# Schematic.net
KiCad netlist of a schematic drawn in Altium Designer
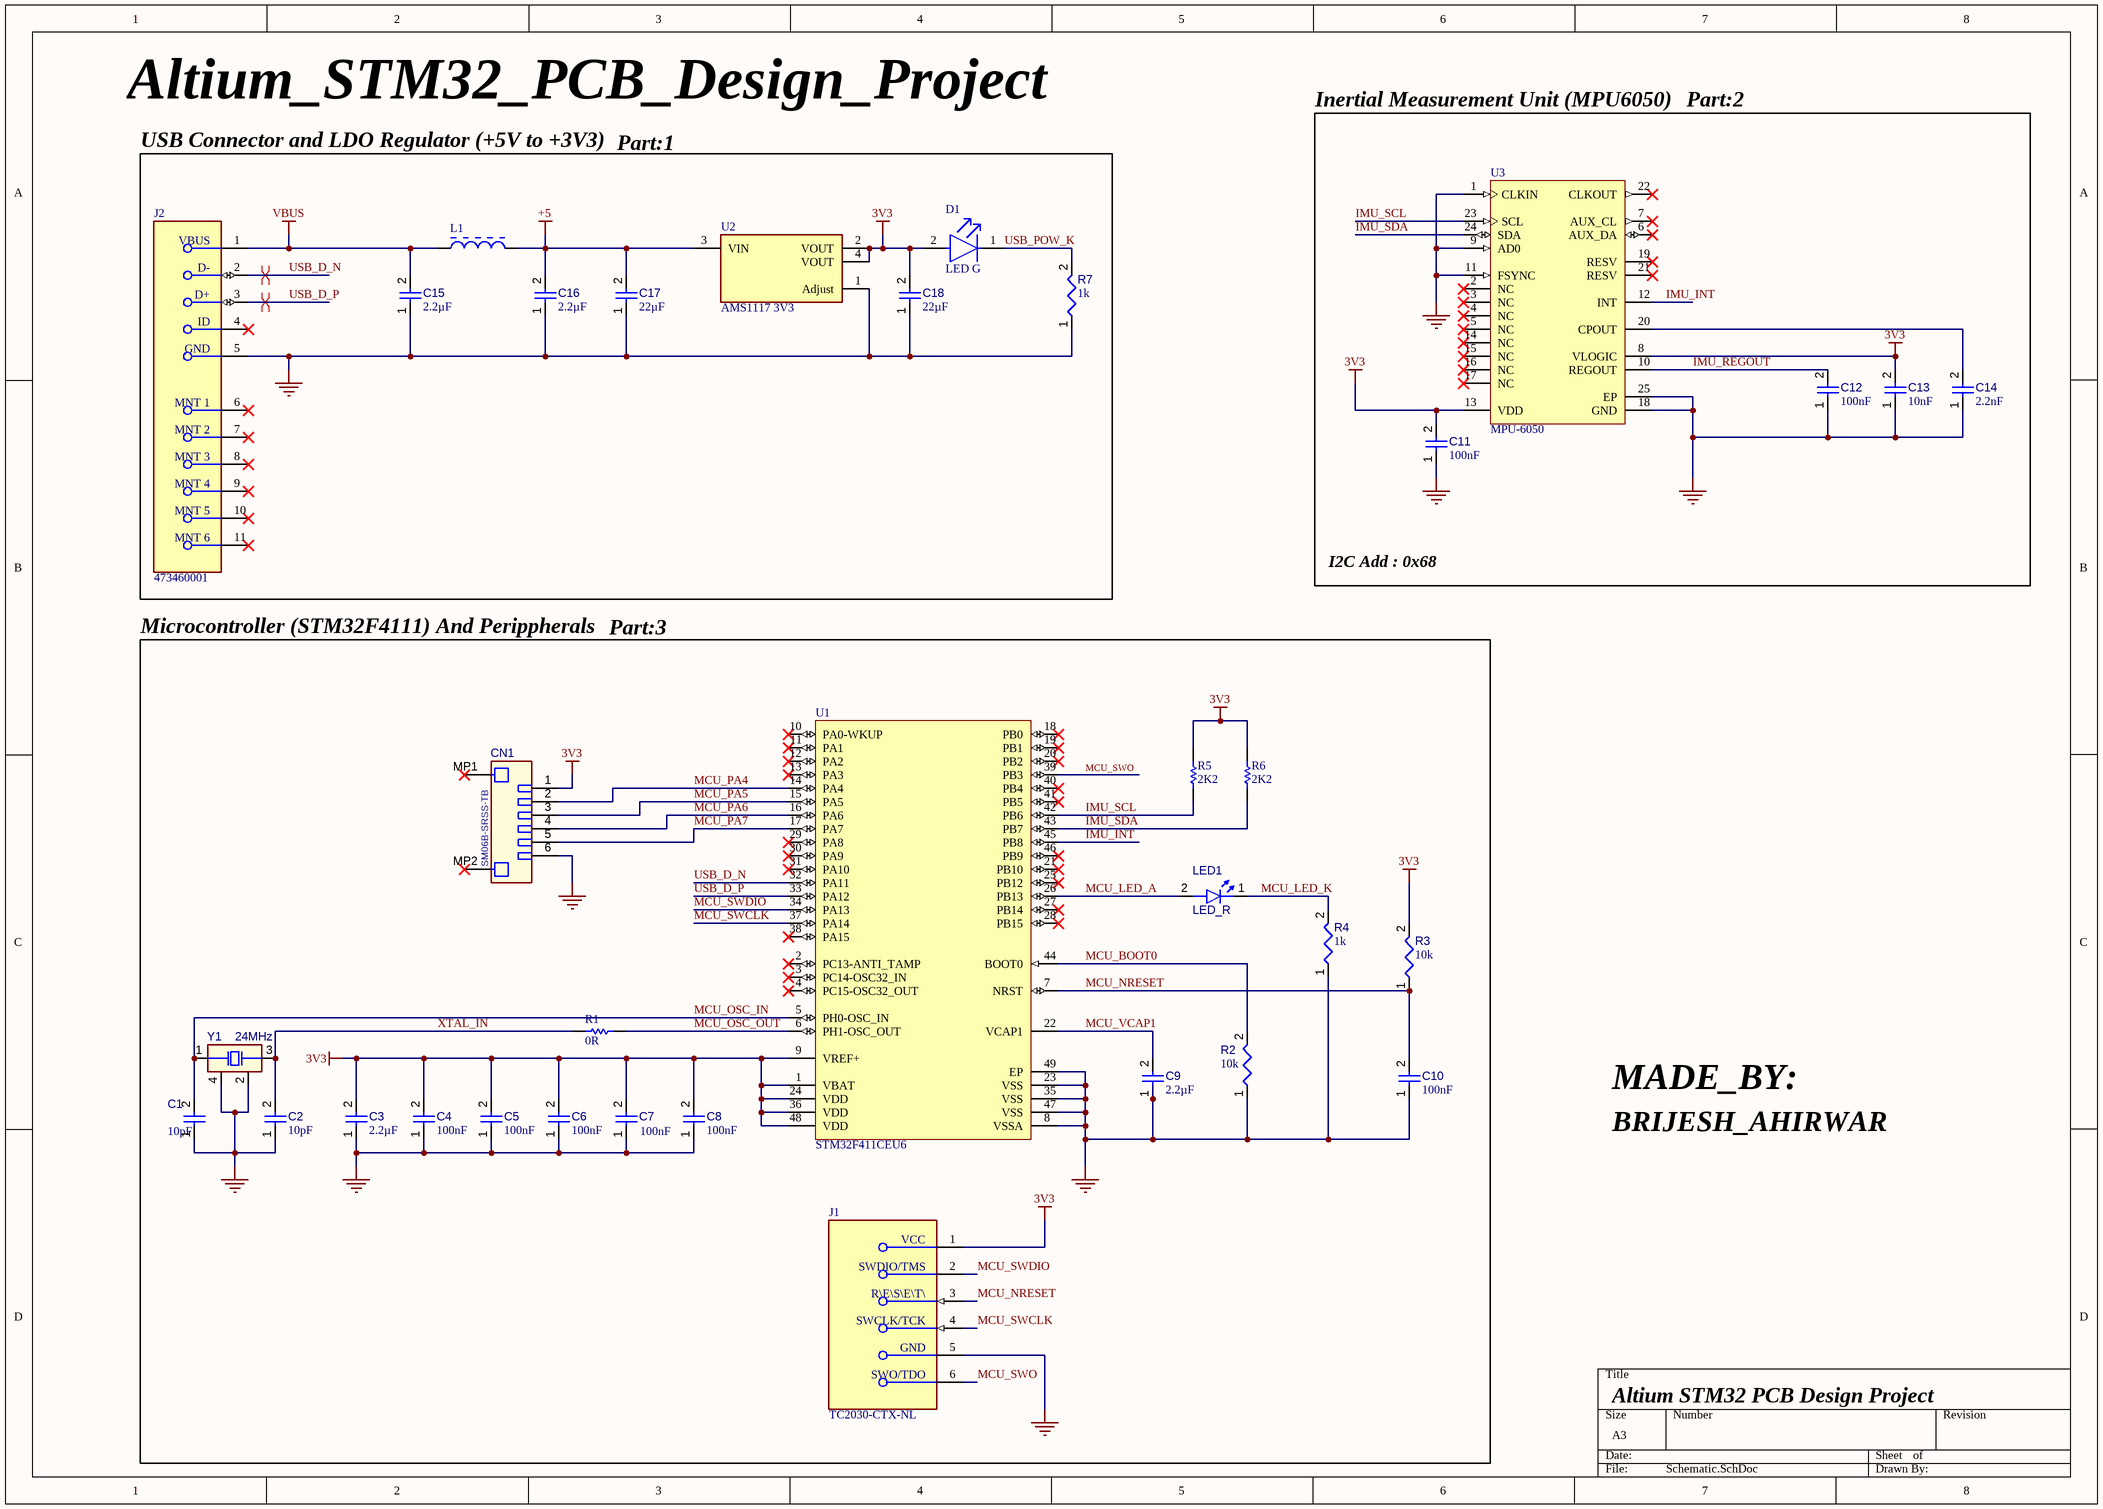
[diagram p0: Schematic.SchDoc]

(export (version "E")
  (design (tool "Eeschema 10.0.6"))
  (components
    (comp (ref "C1")
      (value "10pF")
      (footprint "CAPC1608X90X40ML10T20")
      (description "Chip Capacitor, 10 pF, +/- 5%, 50 V, 0603 (1608 Metric)")
      (fields (field (name "TOLERANCE") "5%") (field (name "Comment") "Capacitor 10 pF +/- 5% 50 V 0603"))
      (libsource (lib "IIT_BHU_Varanasi") (part "CAP-NP-2"))
    )
    (comp (ref "C2")
      (value "10pF")
      (footprint "CAPC1608X90X40ML10T20")
      (description "Chip Capacitor, 10 pF, +/- 5%, 50 V, 0603 (1608 Metric)")
      (fields (field (name "TOLERANCE") "5%") (field (name "Comment") "Capacitor 10 pF +/- 5% 50 V 0603"))
      (libsource (lib "IIT_BHU_Varanasi") (part "CAP-NP-2"))
    )
    (comp (ref "C3")
      (value "2.2µF")
      (footprint "CAPC0603(1608)100_L")
      (description "Chip Capacitor, 10µF +/-20%, 10V, 0603, Thickness 1 mm")
      (fields (field (name "TOLERANCE") "10%") (field (name "Comment") "Capacitor 10µF +/-20% 10V 0603"))
      (libsource (lib "IIT_BHU_Varanasi") (part "CAP-NP-2"))
    )
    (comp (ref "C4")
      (value "100nF")
      (footprint "CAPC1005X56X25LL10T15")
      (description "Chip Capacitor, 0.1 uF, +/- 5%, 16 V, 0402 (1005 Metric)")
      (fields (field (name "TOLERANCE") "5%") (field (name "Comment") "Capacitor 0.1 uF +/- 5% 16 V 0402"))
      (libsource (lib "IIT_BHU_Varanasi") (part "CAP-NP-2"))
    )
    (comp (ref "C5")
      (value "100nF")
      (footprint "CAPC1005X56X25LL10T15")
      (description "Chip Capacitor, 0.1 uF, +/- 5%, 16 V, 0402 (1005 Metric)")
      (fields (field (name "TOLERANCE") "5%") (field (name "Comment") "Capacitor 0.1 uF +/- 5% 16 V 0402"))
      (libsource (lib "IIT_BHU_Varanasi") (part "CAP-NP-2"))
    )
    (comp (ref "C6")
      (value "100nF")
      (footprint "CAPC1005X56X25LL10T15")
      (description "Chip Capacitor, 0.1 uF, +/- 5%, 16 V, 0402 (1005 Metric)")
      (fields (field (name "TOLERANCE") "5%") (field (name "Comment") "Capacitor 0.1 uF +/- 5% 16 V 0402"))
      (libsource (lib "IIT_BHU_Varanasi") (part "CAP-NP-2"))
    )
    (comp (ref "C7")
      (value "100nF")
      (footprint "CAPC1005X56X25LL10T15")
      (description "Chip Capacitor, 0.1 uF, +/- 5%, 16 V, 0402 (1005 Metric)")
      (fields (field (name "TOLERANCE") "5%") (field (name "Comment") "Capacitor 0.1 uF +/- 5% 16 V 0402"))
      (libsource (lib "IIT_BHU_Varanasi") (part "CAP-NP-2"))
    )
    (comp (ref "C8")
      (value "100nF")
      (footprint "CAPC1005X56X25LL10T15")
      (description "Chip Capacitor, 0.1 uF, +/- 5%, 16 V, 0402 (1005 Metric)")
      (fields (field (name "TOLERANCE") "5%") (field (name "Comment") "Capacitor 0.1 uF +/- 5% 16 V 0402"))
      (libsource (lib "IIT_BHU_Varanasi") (part "CAP-NP-2"))
    )
    (comp (ref "C9")
      (value "2.2µF")
      (footprint "CAPC0603(1608)100_L")
      (description "Chip Capacitor, 10µF +/-20%, 10V, 0603, Thickness 1 mm")
      (fields (field (name "TOLERANCE") "10%") (field (name "Comment") "Capacitor 10µF +/-20% 10V 0603"))
      (libsource (lib "IIT_BHU_Varanasi") (part "CAP-NP-2"))
    )
    (comp (ref "C10")
      (value "100nF")
      (footprint "CAPC1005X56X25LL10T15")
      (description "Chip Capacitor, 0.1 uF, +/- 5%, 16 V, 0402 (1005 Metric)")
      (fields (field (name "TOLERANCE") "5%") (field (name "Comment") "Capacitor 0.1 uF +/- 5% 16 V 0402"))
      (libsource (lib "IIT_BHU_Varanasi") (part "CAP-NP-2"))
    )
    (comp (ref "C11")
      (value "100nF")
      (footprint "CAPC1005X56X25LL10T15")
      (description "Chip Capacitor, 0.1 uF, +/- 5%, 16 V, 0402 (1005 Metric)")
      (fields (field (name "TOLERANCE") "5%") (field (name "Comment") "Capacitor 0.1 uF +/- 5% 16 V 0402"))
      (libsource (lib "IIT_BHU_Varanasi") (part "CAP-NP-2"))
    )
    (comp (ref "C12")
      (value "100nF")
      (footprint "CAPC1005X56X25LL10T15")
      (description "Chip Capacitor, 0.1 uF, +/- 5%, 16 V, 0402 (1005 Metric)")
      (fields (field (name "TOLERANCE") "5%") (field (name "Comment") "Capacitor 0.1 uF +/- 5% 16 V 0402"))
      (libsource (lib "IIT_BHU_Varanasi") (part "CAP-NP-2"))
    )
    (comp (ref "C13")
      (value "10nF")
      (footprint "CAPC1005X56X25LL10T15")
      (description "Chip Capacitor, 0.1 uF, +/- 5%, 16 V, 0402 (1005 Metric)")
      (fields (field (name "TOLERANCE") "5%") (field (name "Comment") "Capacitor 0.1 uF +/- 5% 16 V 0402"))
      (libsource (lib "IIT_BHU_Varanasi") (part "CAP-NP-2"))
    )
    (comp (ref "C14")
      (value "2.2nF")
      (footprint "CAPC1005X56X25LL10T15")
      (description "Chip Capacitor, 0.1 uF, +/- 5%, 16 V, 0402 (1005 Metric)")
      (fields (field (name "TOLERANCE") "5%") (field (name "Comment") "Capacitor 0.1 uF +/- 5% 16 V 0402"))
      (libsource (lib "IIT_BHU_Varanasi") (part "CAP-NP-2"))
    )
    (comp (ref "C15")
      (value "2.2µF")
      (footprint "CAPC0603(1608)100_L")
      (description "Chip Capacitor, 10µF +/-20%, 10V, 0603, Thickness 1 mm")
      (fields (field (name "TOLERANCE") "10%") (field (name "Comment") "Capacitor 10µF +/-20% 10V 0603"))
      (libsource (lib "IIT_BHU_Varanasi") (part "CAP-NP-2"))
    )
    (comp (ref "C16")
      (value "2.2µF")
      (footprint "CAPC0603(1608)100_L")
      (description "Chip Capacitor, 10µF +/-20%, 10V, 0603, Thickness 1 mm")
      (fields (field (name "TOLERANCE") "10%") (field (name "Comment") "Capacitor 10µF +/-20% 10V 0603"))
      (libsource (lib "IIT_BHU_Varanasi") (part "CAP-NP-2"))
    )
    (comp (ref "C17")
      (value "22µF")
      (footprint "CAPC0603(1608)100_L")
      (description "Chip Capacitor, 10µF +/-20%, 10V, 0603, Thickness 1 mm")
      (fields (field (name "TOLERANCE") "10%") (field (name "Comment") "Capacitor 10µF +/-20% 10V 0603"))
      (libsource (lib "IIT_BHU_Varanasi") (part "CAP-NP-2"))
    )
    (comp (ref "C18")
      (value "22µF")
      (footprint "CAPC0603(1608)100_L")
      (description "Chip Capacitor, 10µF +/-20%, 10V, 0603, Thickness 1 mm")
      (fields (field (name "TOLERANCE") "10%") (field (name "Comment") "Capacitor 10µF +/-20% 10V 0603"))
      (libsource (lib "IIT_BHU_Varanasi") (part "CAP-NP-2"))
    )
    (comp (ref "CN1")
      (value "SM06B-SRSS-TB")
      (footprint "JST-SM06B-SRSS-TB_V")
      (description "Male Header, Pitch 1 mm, 1 x 6 Position, Height 2.95 mm, -25 to 85 degC, RoHS, Tape and Reel")
      (libsource (lib "IIT_BHU_Varanasi") (part "CMP-00143-5"))
    )
    (comp (ref "D1")
      (value "LED G")
      (footprint "FP-LG_Q396-MFG")
      (description "LED GREEN DIFFUSED 0603 SMD")
      (libsource (lib "Altium Content Vault") (part "8706943c75ba83719d021d2fdc84c58"))
    )
    (comp (ref "J1")
      (value "TC2030-CTX-NL")
      (footprint "FP-TC2030-CTX-NL-MFG")
      (description "6-Pin “No legs” TC2030 Plug-of-Nails™ Cable for use with ARM Cortex processors")
      (libsource (lib "Altium Content Vault") (part "e3fe093a55dc37473f431e03719485e"))
    )
    (comp (ref "J2")
      (value "473460001")
      (footprint "FP-473460001-MFG")
      (description "CONN RCPT USB2.0 MICRO B SMD R/A")
      (fields
        (field (name "OCTOPART") "https://octopart.com/47346-0001-molex-7164928")
        (field (name "MANUFACTURER") "Molex")
      )
      (libsource (lib "Altium Content Vault") (part "53ae1f1d9b557310b43ca686e5bb76a"))
    )
    (comp (ref "L1")
      (value "BLM18AG121SN1D")
      (footprint "MURA-BLM18-F-H1-CHIP-2_V")
      (fields (field (name "TOLERANCE") "25%") (field (name "MANUFACTURER") "Murata"))
      (libsource (lib "IIT_BHU_Varanasi") (part "IND-FB-2"))
    )
    (comp (ref "LED1")
      (value "LED_R")
      (footprint "QTB-QBLP595_V")
      (description "Chip LED 0402, Red, 0.02 A, 2.0 to 2.5 V, -40 to 80 degC, 2-Pin SMD, RoHS, Tape and Reel")
      (libsource (lib "IIT_BHU_Varanasi") (part "LED-KA-2"))
    )
    (comp (ref "R1")
      (value "0R")
      (footprint "RESC1005X40X25ML05T10")
      (description "Chip Resistor, 0 Ohm, 0.063 W, -55 to 155 degC, 0402 (1005 Metric)")
      (fields (field (name "POWER") "63mW") (field (name "Comment") "Resistor 0R 0402 63 mW"))
      (libsource (lib "") (part "RES-2_1"))
    )
    (comp (ref "R2")
      (value "10k")
      (footprint "RESC0402(1005)_L")
      (description "Chip Resistor, 10 kOhms, +/-1 %, 63 mW, -55 to 125 degC, 0402")
      (fields (field (name "POWER") "63mW") (field (name "TOLERANCE") "1%"))
      (libsource (lib "IIT_BHU_Varanasi") (part "RES-2"))
    )
    (comp (ref "R3")
      (value "10k")
      (footprint "RESC0402(1005)_L")
      (description "Chip Resistor, 10 kOhms, +/-1 %, 63 mW, -55 to 125 degC, 0402")
      (fields (field (name "POWER") "63mW") (field (name "TOLERANCE") "1%"))
      (libsource (lib "IIT_BHU_Varanasi") (part "RES-2"))
    )
    (comp (ref "R4")
      (value "1k")
      (footprint "RESC0402(1005)_L")
      (description "Chip Resistor, 1 kOhms, +/-5 %, 63 mW, -55 to 155 degC, 0402")
      (fields (field (name "TOLERANCE") "5%") (field (name "POWER") "63mW"))
      (libsource (lib "IIT_BHU_Varanasi") (part "RES-2"))
    )
    (comp (ref "R5")
      (value "2K2")
      (footprint "RESC0402(1005)_N")
      (description "2K2 0.063W 5% 0402 (1005 Metric)  SMD")
      (fields (field (name "TOLERANCE") "5 %") (field (name "POWER") "0.063 W"))
      (libsource (lib "Altium Content Vault") (part "RES"))
    )
    (comp (ref "R6")
      (value "2K2")
      (footprint "RESC0402(1005)_N")
      (description "2K2 0.063W 5% 0402 (1005 Metric)  SMD")
      (fields (field (name "TOLERANCE") "5 %") (field (name "POWER") "0.063 W"))
      (libsource (lib "Altium Content Vault") (part "RES"))
    )
    (comp (ref "R7")
      (value "1k")
      (footprint "RESC0402(1005)_L")
      (description "Chip Resistor, 1 kOhms, +/-5 %, 63 mW, -55 to 155 degC, 0402")
      (fields (field (name "TOLERANCE") "5%") (field (name "POWER") "63mW"))
      (libsource (lib "IIT_BHU_Varanasi") (part "RES-2"))
    )
    (comp (ref "U1")
      (value "STM32F411CEU6")
      (footprint "STM-UFQFPN48_L")
      (libsource (lib "Altium Content Vault") (part "MC-ARM-STM32F411-UFQFPN48"))
    )
    (comp (ref "U2")
      (value "AMS1117 3V3")
      (footprint "FP-ams1117-IPC_C")
      (description "1A LOW DROPOUT VOLTAGE REGULATOR")
      (libsource (lib "Altium Content Vault") (part "59ad430b93a2c51b3e6ee7c3b069677"))
    )
    (comp (ref "U3")
      (value "MPU-6050")
      (footprint "IS-QFN-24_V")
      (fields (field (name "MANUFACTURER") "InvenSense"))
      (libsource (lib "Altium Content Vault") (part "IS-MPU-6050-QFN-24"))
    )
    (comp (ref "Y1")
      (value "24MHz")
      (footprint "EPSON-FA-128_V")
      (description "Crystal, 24 MHz, +/- 10 ppm, -20 to 75 degC, 4-Pin SMD, RoHS, Tape and Reel")
      (libsource (lib "IIT_BHU_Varanasi") (part "CMP-00014-7"))
    )
  )
  (nets
    (net (code "1") (name "+5") (class "Default")
      (node (ref "C16") (pin "2") (pinfunction "2_2") (pintype "passive"))
      (node (ref "C17") (pin "2") (pinfunction "2_2") (pintype "passive"))
      (node (ref "L1") (pin "2") (pinfunction "2_2") (pintype "passive"))
      (node (ref "U2") (pin "3") (pinfunction "VIN_3") (pintype "power_in"))
    )
    (net (code "2") (name "/IMU_INT") (class "Default")
      (node (ref "U1") (pin "45") (pinfunction "PB8_45") (pintype "bidirectional"))
      (node (ref "U3") (pin "12") (pinfunction "INT_12") (pintype "open_collector"))
    )
    (net (code "3") (name "/IMU_REGOUT") (class "Default")
      (node (ref "C12") (pin "2") (pinfunction "2_2") (pintype "passive"))
      (node (ref "U3") (pin "10") (pinfunction "REGOUT_10") (pintype "passive"))
    )
    (net (code "4") (name "/IMU_SCL") (class "Default")
      (node (ref "R5") (pin "1") (pinfunction "1_1") (pintype "passive"))
      (node (ref "U1") (pin "42") (pinfunction "PB6_42") (pintype "bidirectional"))
      (node (ref "U3") (pin "23") (pinfunction "SCL_23") (pintype "input"))
    )
    (net (code "5") (name "/IMU_SDA") (class "Default")
      (node (ref "R6") (pin "1") (pinfunction "1_1") (pintype "passive"))
      (node (ref "U1") (pin "43") (pinfunction "PB7_43") (pintype "bidirectional"))
      (node (ref "U3") (pin "24") (pinfunction "SDA_24") (pintype "bidirectional"))
    )
    (net (code "6") (name "/MCU_BOOT0") (class "Default")
      (node (ref "R2") (pin "2") (pinfunction "2_2") (pintype "passive"))
      (node (ref "U1") (pin "44") (pinfunction "BOOT0_44") (pintype "input"))
    )
    (net (code "7") (name "/MCU_LED_A") (class "Default")
      (node (ref "LED1") (pin "2") (pinfunction "A_2") (pintype "passive"))
      (node (ref "U1") (pin "26") (pinfunction "PB13_26") (pintype "bidirectional"))
    )
    (net (code "8") (name "/MCU_LED_K") (class "Default")
      (node (ref "LED1") (pin "1") (pinfunction "K_1") (pintype "passive"))
      (node (ref "R4") (pin "2") (pinfunction "2_2") (pintype "passive"))
    )
    (net (code "9") (name "/MCU_NRESET") (class "Default")
      (node (ref "C10") (pin "2") (pinfunction "2_2") (pintype "passive"))
      (node (ref "J1") (pin "3") (pinfunction "~{RESET}_3") (pintype "input"))
      (node (ref "R3") (pin "1") (pinfunction "1_1") (pintype "passive"))
      (node (ref "U1") (pin "7") (pinfunction "NRST_7") (pintype "bidirectional"))
    )
    (net (code "10") (name "/MCU_OSC_IN") (class "Default")
      (node (ref "C1") (pin "2") (pinfunction "2_2") (pintype "passive"))
      (node (ref "U1") (pin "5") (pinfunction "PH0-OSC_IN_5") (pintype "bidirectional"))
      (node (ref "Y1") (pin "1") (pinfunction "X1_1") (pintype "passive"))
    )
    (net (code "11") (name "/MCU_OSC_OUT") (class "Default")
      (node (ref "R1") (pin "2") (pinfunction "2_2") (pintype "passive"))
      (node (ref "U1") (pin "6") (pinfunction "PH1-OSC_OUT_6") (pintype "bidirectional"))
    )
    (net (code "12") (name "/MCU_PA4") (class "Default")
      (node (ref "CN1") (pin "2") (pinfunction "2_2") (pintype "passive"))
      (node (ref "U1") (pin "14") (pinfunction "PA4_14") (pintype "bidirectional"))
    )
    (net (code "13") (name "/MCU_PA5") (class "Default")
      (node (ref "CN1") (pin "3") (pinfunction "3_3") (pintype "passive"))
      (node (ref "U1") (pin "15") (pinfunction "PA5_15") (pintype "bidirectional"))
    )
    (net (code "14") (name "/MCU_PA6") (class "Default")
      (node (ref "CN1") (pin "4") (pinfunction "4_4") (pintype "passive"))
      (node (ref "U1") (pin "16") (pinfunction "PA6_16") (pintype "bidirectional"))
    )
    (net (code "15") (name "/MCU_PA7") (class "Default")
      (node (ref "CN1") (pin "5") (pinfunction "5_5") (pintype "passive"))
      (node (ref "U1") (pin "17") (pinfunction "PA7_17") (pintype "bidirectional"))
    )
    (net (code "16") (name "/MCU_SWCLK") (class "Default")
      (node (ref "J1") (pin "4") (pinfunction "SWCLK/TCK_4") (pintype "input"))
      (node (ref "U1") (pin "37") (pinfunction "PA14_37") (pintype "bidirectional"))
    )
    (net (code "17") (name "/MCU_SWDIO") (class "Default")
      (node (ref "J1") (pin "2") (pinfunction "SWDIO/TMS_2") (pintype "passive"))
      (node (ref "U1") (pin "34") (pinfunction "PA13_34") (pintype "bidirectional"))
    )
    (net (code "18") (name "/MCU_SWO") (class "Default")
      (node (ref "J1") (pin "6") (pinfunction "SWO/TDO_6") (pintype "passive"))
      (node (ref "U1") (pin "39") (pinfunction "PB3_39") (pintype "bidirectional"))
    )
    (net (code "19") (name "/MCU_VCAP1") (class "Default")
      (node (ref "C9") (pin "2") (pinfunction "2_2") (pintype "passive"))
      (node (ref "U1") (pin "22") (pinfunction "VCAP1_22") (pintype "passive"))
    )
    (net (code "20") (name "/USB_D_N") (class "Default")
      (node (ref "J2") (pin "2") (pinfunction "D-_2") (pintype "bidirectional"))
      (node (ref "U1") (pin "32") (pinfunction "PA11_32") (pintype "bidirectional"))
    )
    (net (code "21") (name "/USB_D_P") (class "Default")
      (node (ref "J2") (pin "3") (pinfunction "D+_3") (pintype "bidirectional"))
      (node (ref "U1") (pin "33") (pinfunction "PA12_33") (pintype "bidirectional"))
    )
    (net (code "22") (name "/USB_POW_K") (class "Default")
      (node (ref "D1") (pin "1") (pinfunction "C_1") (pintype "passive"))
      (node (ref "R7") (pin "2") (pinfunction "2_2") (pintype "passive"))
    )
    (net (code "23") (name "/XTAL_IN") (class "Default")
      (node (ref "C2") (pin "2") (pinfunction "2_2") (pintype "passive"))
      (node (ref "R1") (pin "1") (pinfunction "1_1") (pintype "passive"))
      (node (ref "Y1") (pin "3") (pinfunction "X2_3") (pintype "passive"))
    )
    (net (code "24") (name "3V3") (class "Default")
      (node (ref "C11") (pin "2") (pinfunction "2_2") (pintype "passive"))
      (node (ref "C13") (pin "2") (pinfunction "2_2") (pintype "passive"))
      (node (ref "C18") (pin "2") (pinfunction "2_2") (pintype "passive"))
      (node (ref "C3") (pin "2") (pinfunction "2_2") (pintype "passive"))
      (node (ref "C4") (pin "2") (pinfunction "2_2") (pintype "passive"))
      (node (ref "C5") (pin "2") (pinfunction "2_2") (pintype "passive"))
      (node (ref "C6") (pin "2") (pinfunction "2_2") (pintype "passive"))
      (node (ref "C7") (pin "2") (pinfunction "2_2") (pintype "passive"))
      (node (ref "C8") (pin "2") (pinfunction "2_2") (pintype "passive"))
      (node (ref "CN1") (pin "1") (pinfunction "1_1") (pintype "passive"))
      (node (ref "D1") (pin "2") (pinfunction "A_2") (pintype "passive"))
      (node (ref "J1") (pin "1") (pinfunction "VCC_1") (pintype "power_in"))
      (node (ref "R3") (pin "2") (pinfunction "2_2") (pintype "passive"))
      (node (ref "R5") (pin "2") (pinfunction "2_2") (pintype "passive"))
      (node (ref "R6") (pin "2") (pinfunction "2_2") (pintype "passive"))
      (node (ref "U1") (pin "1") (pinfunction "VBAT_1") (pintype "power_in"))
      (node (ref "U1") (pin "24") (pinfunction "VDD_24") (pintype "power_in"))
      (node (ref "U1") (pin "36") (pinfunction "VDD_36") (pintype "power_in"))
      (node (ref "U1") (pin "48") (pinfunction "VDD_48") (pintype "power_in"))
      (node (ref "U1") (pin "9") (pinfunction "VREF+_9") (pintype "power_in"))
      (node (ref "U2") (pin "2") (pinfunction "VOUT_2") (pintype "passive"))
      (node (ref "U2") (pin "4") (pinfunction "VOUT_4") (pintype "passive"))
      (node (ref "U3") (pin "13") (pinfunction "VDD_13") (pintype "power_in"))
      (node (ref "U3") (pin "8") (pinfunction "VLOGIC_8") (pintype "power_in"))
    )
    (net (code "25") (name "GND") (class "Default")
      (node (ref "C1") (pin "1") (pinfunction "1_1") (pintype "passive"))
      (node (ref "C10") (pin "1") (pinfunction "1_1") (pintype "passive"))
      (node (ref "C11") (pin "1") (pinfunction "1_1") (pintype "passive"))
      (node (ref "C12") (pin "1") (pinfunction "1_1") (pintype "passive"))
      (node (ref "C13") (pin "1") (pinfunction "1_1") (pintype "passive"))
      (node (ref "C14") (pin "1") (pinfunction "1_1") (pintype "passive"))
      (node (ref "C15") (pin "1") (pinfunction "1_1") (pintype "passive"))
      (node (ref "C16") (pin "1") (pinfunction "1_1") (pintype "passive"))
      (node (ref "C17") (pin "1") (pinfunction "1_1") (pintype "passive"))
      (node (ref "C18") (pin "1") (pinfunction "1_1") (pintype "passive"))
      (node (ref "C2") (pin "1") (pinfunction "1_1") (pintype "passive"))
      (node (ref "C3") (pin "1") (pinfunction "1_1") (pintype "passive"))
      (node (ref "C4") (pin "1") (pinfunction "1_1") (pintype "passive"))
      (node (ref "C5") (pin "1") (pinfunction "1_1") (pintype "passive"))
      (node (ref "C6") (pin "1") (pinfunction "1_1") (pintype "passive"))
      (node (ref "C7") (pin "1") (pinfunction "1_1") (pintype "passive"))
      (node (ref "C8") (pin "1") (pinfunction "1_1") (pintype "passive"))
      (node (ref "C9") (pin "1") (pinfunction "1_1") (pintype "passive"))
      (node (ref "CN1") (pin "6") (pinfunction "6_6") (pintype "passive"))
      (node (ref "J1") (pin "5") (pinfunction "GND_5") (pintype "power_in"))
      (node (ref "J2") (pin "5") (pinfunction "GND_5") (pintype "power_in"))
      (node (ref "R2") (pin "1") (pinfunction "1_1") (pintype "passive"))
      (node (ref "R4") (pin "1") (pinfunction "1_1") (pintype "passive"))
      (node (ref "R7") (pin "1") (pinfunction "1_1") (pintype "passive"))
      (node (ref "U1") (pin "23") (pinfunction "VSS_23") (pintype "power_in"))
      (node (ref "U1") (pin "35") (pinfunction "VSS_35") (pintype "power_in"))
      (node (ref "U1") (pin "47") (pinfunction "VSS_47") (pintype "power_in"))
      (node (ref "U1") (pin "49") (pinfunction "EP_49") (pintype "power_in"))
      (node (ref "U1") (pin "8") (pinfunction "VSSA_8") (pintype "power_in"))
      (node (ref "U2") (pin "1") (pinfunction "Adjust_1") (pintype "passive"))
      (node (ref "U3") (pin "1") (pinfunction "CLKIN_1") (pintype "input"))
      (node (ref "U3") (pin "11") (pinfunction "FSYNC_11") (pintype "input"))
      (node (ref "U3") (pin "18") (pinfunction "GND_18") (pintype "power_in"))
      (node (ref "U3") (pin "25") (pinfunction "EP_25") (pintype "power_in"))
      (node (ref "U3") (pin "9") (pinfunction "AD0_9") (pintype "input"))
      (node (ref "Y1") (pin "2") (pinfunction "NC_2") (pintype "power_in"))
      (node (ref "Y1") (pin "4") (pinfunction "NC_4") (pintype "power_in"))
    )
    (net (code "26") (name "Net-(U3-CPOUT)") (class "Default")
      (node (ref "C14") (pin "2") (pinfunction "2_2") (pintype "passive"))
      (node (ref "U3") (pin "20") (pinfunction "CPOUT_20") (pintype "passive"))
    )
    (net (code "27") (name "VBUS") (class "Default")
      (node (ref "C15") (pin "2") (pinfunction "2_2") (pintype "passive"))
      (node (ref "J2") (pin "1") (pinfunction "VBUS_1") (pintype "power_in"))
      (node (ref "L1") (pin "1") (pinfunction "1_1") (pintype "passive"))
    )
    (net (code "28") (name "unconnected-(CN1-PadMP1)") (class "Default")
      (node (ref "CN1") (pin "MP1") (pinfunction "MP1_MP1") (pintype "passive+no_connect"))
    )
    (net (code "29") (name "unconnected-(CN1-PadMP2)") (class "Default")
      (node (ref "CN1") (pin "MP2") (pinfunction "MP2_MP2") (pintype "passive+no_connect"))
    )
    (net (code "30") (name "unconnected-(J2-ID-Pad4)") (class "Default")
      (node (ref "J2") (pin "4") (pinfunction "ID_4") (pintype "passive+no_connect"))
    )
    (net (code "31") (name "unconnected-(J2-MNT_1-Pad6)") (class "Default")
      (node (ref "J2") (pin "6") (pinfunction "MNT_1_6") (pintype "passive+no_connect"))
    )
    (net (code "32") (name "unconnected-(J2-MNT_2-Pad7)") (class "Default")
      (node (ref "J2") (pin "7") (pinfunction "MNT_2_7") (pintype "passive+no_connect"))
    )
    (net (code "33") (name "unconnected-(J2-MNT_3-Pad8)") (class "Default")
      (node (ref "J2") (pin "8") (pinfunction "MNT_3_8") (pintype "passive+no_connect"))
    )
    (net (code "34") (name "unconnected-(J2-MNT_4-Pad9)") (class "Default")
      (node (ref "J2") (pin "9") (pinfunction "MNT_4_9") (pintype "passive+no_connect"))
    )
    (net (code "35") (name "unconnected-(J2-MNT_5-Pad10)") (class "Default")
      (node (ref "J2") (pin "10") (pinfunction "MNT_5_10") (pintype "passive+no_connect"))
    )
    (net (code "36") (name "unconnected-(J2-MNT_6-Pad11)") (class "Default")
      (node (ref "J2") (pin "11") (pinfunction "MNT_6_11") (pintype "passive+no_connect"))
    )
    (net (code "37") (name "unconnected-(U1-PA0-WKUP-Pad10)") (class "Default")
      (node (ref "U1") (pin "10") (pinfunction "PA0-WKUP_10") (pintype "bidirectional+no_connect"))
    )
    (net (code "38") (name "unconnected-(U1-PA1-Pad11)") (class "Default")
      (node (ref "U1") (pin "11") (pinfunction "PA1_11") (pintype "bidirectional+no_connect"))
    )
    (net (code "39") (name "unconnected-(U1-PA2-Pad12)") (class "Default")
      (node (ref "U1") (pin "12") (pinfunction "PA2_12") (pintype "bidirectional+no_connect"))
    )
    (net (code "40") (name "unconnected-(U1-PA3-Pad13)") (class "Default")
      (node (ref "U1") (pin "13") (pinfunction "PA3_13") (pintype "bidirectional+no_connect"))
    )
    (net (code "41") (name "unconnected-(U1-PA8-Pad29)") (class "Default")
      (node (ref "U1") (pin "29") (pinfunction "PA8_29") (pintype "bidirectional+no_connect"))
    )
    (net (code "42") (name "unconnected-(U1-PA9-Pad30)") (class "Default")
      (node (ref "U1") (pin "30") (pinfunction "PA9_30") (pintype "bidirectional+no_connect"))
    )
    (net (code "43") (name "unconnected-(U1-PA10-Pad31)") (class "Default")
      (node (ref "U1") (pin "31") (pinfunction "PA10_31") (pintype "bidirectional+no_connect"))
    )
    (net (code "44") (name "unconnected-(U1-PA15-Pad38)") (class "Default")
      (node (ref "U1") (pin "38") (pinfunction "PA15_38") (pintype "bidirectional+no_connect"))
    )
    (net (code "45") (name "unconnected-(U1-PB0-Pad18)") (class "Default")
      (node (ref "U1") (pin "18") (pinfunction "PB0_18") (pintype "bidirectional+no_connect"))
    )
    (net (code "46") (name "unconnected-(U1-PB1-Pad19)") (class "Default")
      (node (ref "U1") (pin "19") (pinfunction "PB1_19") (pintype "bidirectional+no_connect"))
    )
    (net (code "47") (name "unconnected-(U1-PB2-Pad20)") (class "Default")
      (node (ref "U1") (pin "20") (pinfunction "PB2_20") (pintype "bidirectional+no_connect"))
    )
    (net (code "48") (name "unconnected-(U1-PB4-Pad40)") (class "Default")
      (node (ref "U1") (pin "40") (pinfunction "PB4_40") (pintype "bidirectional+no_connect"))
    )
    (net (code "49") (name "unconnected-(U1-PB5-Pad41)") (class "Default")
      (node (ref "U1") (pin "41") (pinfunction "PB5_41") (pintype "bidirectional+no_connect"))
    )
    (net (code "50") (name "unconnected-(U1-PB9-Pad46)") (class "Default")
      (node (ref "U1") (pin "46") (pinfunction "PB9_46") (pintype "bidirectional+no_connect"))
    )
    (net (code "51") (name "unconnected-(U1-PB10-Pad21)") (class "Default")
      (node (ref "U1") (pin "21") (pinfunction "PB10_21") (pintype "bidirectional+no_connect"))
    )
    (net (code "52") (name "unconnected-(U1-PB12-Pad25)") (class "Default")
      (node (ref "U1") (pin "25") (pinfunction "PB12_25") (pintype "bidirectional+no_connect"))
    )
    (net (code "53") (name "unconnected-(U1-PB14-Pad27)") (class "Default")
      (node (ref "U1") (pin "27") (pinfunction "PB14_27") (pintype "bidirectional+no_connect"))
    )
    (net (code "54") (name "unconnected-(U1-PB15-Pad28)") (class "Default")
      (node (ref "U1") (pin "28") (pinfunction "PB15_28") (pintype "bidirectional+no_connect"))
    )
    (net (code "55") (name "unconnected-(U1-PC13-ANTI_TAMP-Pad2)") (class "Default")
      (node (ref "U1") (pin "2") (pinfunction "PC13-ANTI_TAMP_2") (pintype "bidirectional+no_connect"))
    )
    (net (code "56") (name "unconnected-(U1-PC14-OSC32_IN-Pad3)") (class "Default")
      (node (ref "U1") (pin "3") (pinfunction "PC14-OSC32_IN_3") (pintype "bidirectional+no_connect"))
    )
    (net (code "57") (name "unconnected-(U1-PC15-OSC32_OUT-Pad4)") (class "Default")
      (node (ref "U1") (pin "4") (pinfunction "PC15-OSC32_OUT_4") (pintype "bidirectional+no_connect"))
    )
    (net (code "58") (name "unconnected-(U3-AUX_CL-Pad7)") (class "Default")
      (node (ref "U3") (pin "7") (pinfunction "AUX_CL_7") (pintype "output+no_connect"))
    )
    (net (code "59") (name "unconnected-(U3-AUX_DA-Pad6)") (class "Default")
      (node (ref "U3") (pin "6") (pinfunction "AUX_DA_6") (pintype "bidirectional+no_connect"))
    )
    (net (code "60") (name "unconnected-(U3-CLKOUT-Pad22)") (class "Default")
      (node (ref "U3") (pin "22") (pinfunction "CLKOUT_22") (pintype "output+no_connect"))
    )
    (net (code "61") (name "unconnected-(U3-NC-Pad2)") (class "Default")
      (node (ref "U3") (pin "2") (pinfunction "NC_2") (pintype "passive+no_connect"))
    )
    (net (code "62") (name "unconnected-(U3-NC-Pad3)") (class "Default")
      (node (ref "U3") (pin "3") (pinfunction "NC_3") (pintype "passive+no_connect"))
    )
    (net (code "63") (name "unconnected-(U3-NC-Pad4)") (class "Default")
      (node (ref "U3") (pin "4") (pinfunction "NC_4") (pintype "passive+no_connect"))
    )
    (net (code "64") (name "unconnected-(U3-NC-Pad5)") (class "Default")
      (node (ref "U3") (pin "5") (pinfunction "NC_5") (pintype "passive+no_connect"))
    )
    (net (code "65") (name "unconnected-(U3-NC-Pad14)") (class "Default")
      (node (ref "U3") (pin "14") (pinfunction "NC_14") (pintype "passive+no_connect"))
    )
    (net (code "66") (name "unconnected-(U3-NC-Pad15)") (class "Default")
      (node (ref "U3") (pin "15") (pinfunction "NC_15") (pintype "passive+no_connect"))
    )
    (net (code "67") (name "unconnected-(U3-NC-Pad16)") (class "Default")
      (node (ref "U3") (pin "16") (pinfunction "NC_16") (pintype "passive+no_connect"))
    )
    (net (code "68") (name "unconnected-(U3-NC-Pad17)") (class "Default")
      (node (ref "U3") (pin "17") (pinfunction "NC_17") (pintype "passive+no_connect"))
    )
    (net (code "69") (name "unconnected-(U3-RESV-Pad19)") (class "Default")
      (node (ref "U3") (pin "19") (pinfunction "RESV_19") (pintype "passive+no_connect"))
    )
    (net (code "70") (name "unconnected-(U3-RESV-Pad21)") (class "Default")
      (node (ref "U3") (pin "21") (pinfunction "RESV_21") (pintype "passive+no_connect"))
    )
  )
)
